# Sheet2.net
KiCad netlist of a schematic drawn in Altium Designer
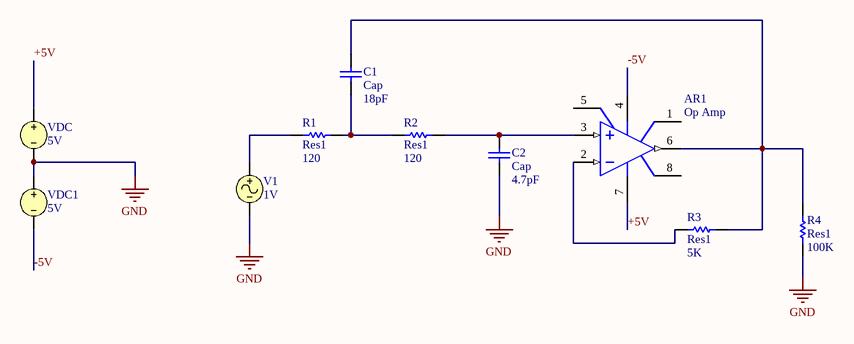
[diagram p0: Sheet2.SchDoc]

(export (version "E")
  (design (tool "Eeschema 10.0.6"))
  (components
    (comp (ref "AR1")
      (value "Op Amp")
      (footprint "H-08A")
      (description "FET Operational Amplifier")
      (fields (field (name "PUBLISHER") "Altium Limited"))
      (libsource (lib "Miscellaneous Devices") (part "Op Amp"))
    )
    (comp (ref "C1")
      (value "Cap")
      (footprint "RAD-0.3")
      (description "Capacitor")
      (fields (field (name "ALTIUM_VALUE") "18pF") (field (name "PUBLISHER") "Altium Limited"))
      (libsource (lib "Miscellaneous Devices") (part "Cap"))
    )
    (comp (ref "C2")
      (value "Cap")
      (footprint "RAD-0.3")
      (description "Capacitor")
      (fields (field (name "ALTIUM_VALUE") "4.7pF") (field (name "PUBLISHER") "Altium Limited"))
      (libsource (lib "Miscellaneous Devices") (part "Cap"))
    )
    (comp (ref "R1")
      (value "Res1")
      (footprint "AXIAL-0.3")
      (description "Resistor")
      (fields (field (name "ALTIUM_VALUE") "120") (field (name "PUBLISHER") "Altium Limited"))
      (libsource (lib "Miscellaneous Devices") (part "Res1"))
    )
    (comp (ref "R2")
      (value "Res1")
      (footprint "AXIAL-0.3")
      (description "Resistor")
      (fields (field (name "ALTIUM_VALUE") "120") (field (name "PUBLISHER") "Altium Limited"))
      (libsource (lib "Miscellaneous Devices") (part "Res1"))
    )
    (comp (ref "R3")
      (value "Res1")
      (footprint "AXIAL-0.3")
      (description "Resistor")
      (fields (field (name "ALTIUM_VALUE") "5K") (field (name "PUBLISHER") "Altium Limited"))
      (libsource (lib "Miscellaneous Devices") (part "Res1"))
    )
    (comp (ref "R4")
      (value "Res1")
      (footprint "AXIAL-0.3")
      (description "Resistor")
      (fields (field (name "ALTIUM_VALUE") "100K") (field (name "PUBLISHER") "Altium Limited"))
      (libsource (lib "Miscellaneous Devices") (part "Res1"))
    )
    (comp (ref "V1")
      (value "1V")
      (description "Sinusoidal Voltage Source")
      (fields (field (name "PUBLISHER") "Altium Limited"))
      (libsource (lib "Simulation Sources") (part "VSIN"))
    )
    (comp (ref "VDC")
      (value "5V")
      (description "Voltage Source")
      (fields (field (name "PUBLISHER") "Altium Limited"))
      (libsource (lib "Simulation Sources") (part "VSRC"))
    )
    (comp (ref "VDC1")
      (value "5V")
      (description "Voltage Source")
      (fields (field (name "PUBLISHER") "Altium Limited"))
      (libsource (lib "Simulation Sources") (part "VSRC"))
    )
  )
  (nets
    (net (code "1") (name "/+5V") (class "Default")
      (node (ref "AR1") (pin "7") (pinfunction "V+_7") (pintype "power_in"))
      (node (ref "VDC") (pin "1") (pinfunction "1_1") (pintype "passive"))
    )
    (net (code "2") (name "/-5V") (class "Default")
      (node (ref "AR1") (pin "4") (pinfunction "V-_4") (pintype "power_in"))
      (node (ref "VDC1") (pin "2") (pinfunction "2_2") (pintype "passive"))
    )
    (net (code "3") (name "GND") (class "Default")
      (node (ref "C2") (pin "1") (pinfunction "1_1") (pintype "passive"))
      (node (ref "R4") (pin "1") (pinfunction "1_1") (pintype "passive"))
      (node (ref "V1") (pin "2") (pinfunction "2_2") (pintype "passive"))
      (node (ref "VDC") (pin "2") (pinfunction "2_2") (pintype "passive"))
      (node (ref "VDC1") (pin "1") (pinfunction "1_1") (pintype "passive"))
    )
    (net (code "4") (name "Net-(AR1-IN+)") (class "Default")
      (node (ref "AR1") (pin "3") (pinfunction "IN+_3") (pintype "input"))
      (node (ref "C2") (pin "2") (pinfunction "2_2") (pintype "passive"))
      (node (ref "R2") (pin "2") (pinfunction "2_2") (pintype "passive"))
    )
    (net (code "5") (name "Net-(AR1-IN-)") (class "Default")
      (node (ref "AR1") (pin "2") (pinfunction "IN-_2") (pintype "input"))
      (node (ref "R3") (pin "1") (pinfunction "1_1") (pintype "passive"))
    )
    (net (code "6") (name "Net-(AR1-OUT)") (class "Default")
      (node (ref "AR1") (pin "6") (pinfunction "OUT_6") (pintype "output"))
      (node (ref "C1") (pin "2") (pinfunction "2_2") (pintype "passive"))
      (node (ref "R3") (pin "2") (pinfunction "2_2") (pintype "passive"))
      (node (ref "R4") (pin "2") (pinfunction "2_2") (pintype "passive"))
    )
    (net (code "7") (name "Net-(C1-Pad1)") (class "Default")
      (node (ref "C1") (pin "1") (pinfunction "1_1") (pintype "passive"))
      (node (ref "R1") (pin "2") (pinfunction "2_2") (pintype "passive"))
      (node (ref "R2") (pin "1") (pinfunction "1_1") (pintype "passive"))
    )
    (net (code "8") (name "Net-(R1-Pad1)") (class "Default")
      (node (ref "R1") (pin "1") (pinfunction "1_1") (pintype "passive"))
      (node (ref "V1") (pin "1") (pinfunction "1_1") (pintype "passive"))
    )
    (net (code "9") (name "unconnected-(AR1-OS_NUL-Pad1)") (class "Default")
      (node (ref "AR1") (pin "1") (pinfunction "OS_NUL_1") (pintype "passive"))
    )
    (net (code "10") (name "unconnected-(AR1-OS_NUL-Pad5)") (class "Default")
      (node (ref "AR1") (pin "5") (pinfunction "OS_NUL_5") (pintype "passive"))
    )
    (net (code "11") (name "unconnected-(AR1-TAB-Pad8)") (class "Default")
      (node (ref "AR1") (pin "8") (pinfunction "TAB_8") (pintype "passive"))
    )
  )
)
